# Charger.net
KiCad netlist of a schematic drawn in Altium Designer
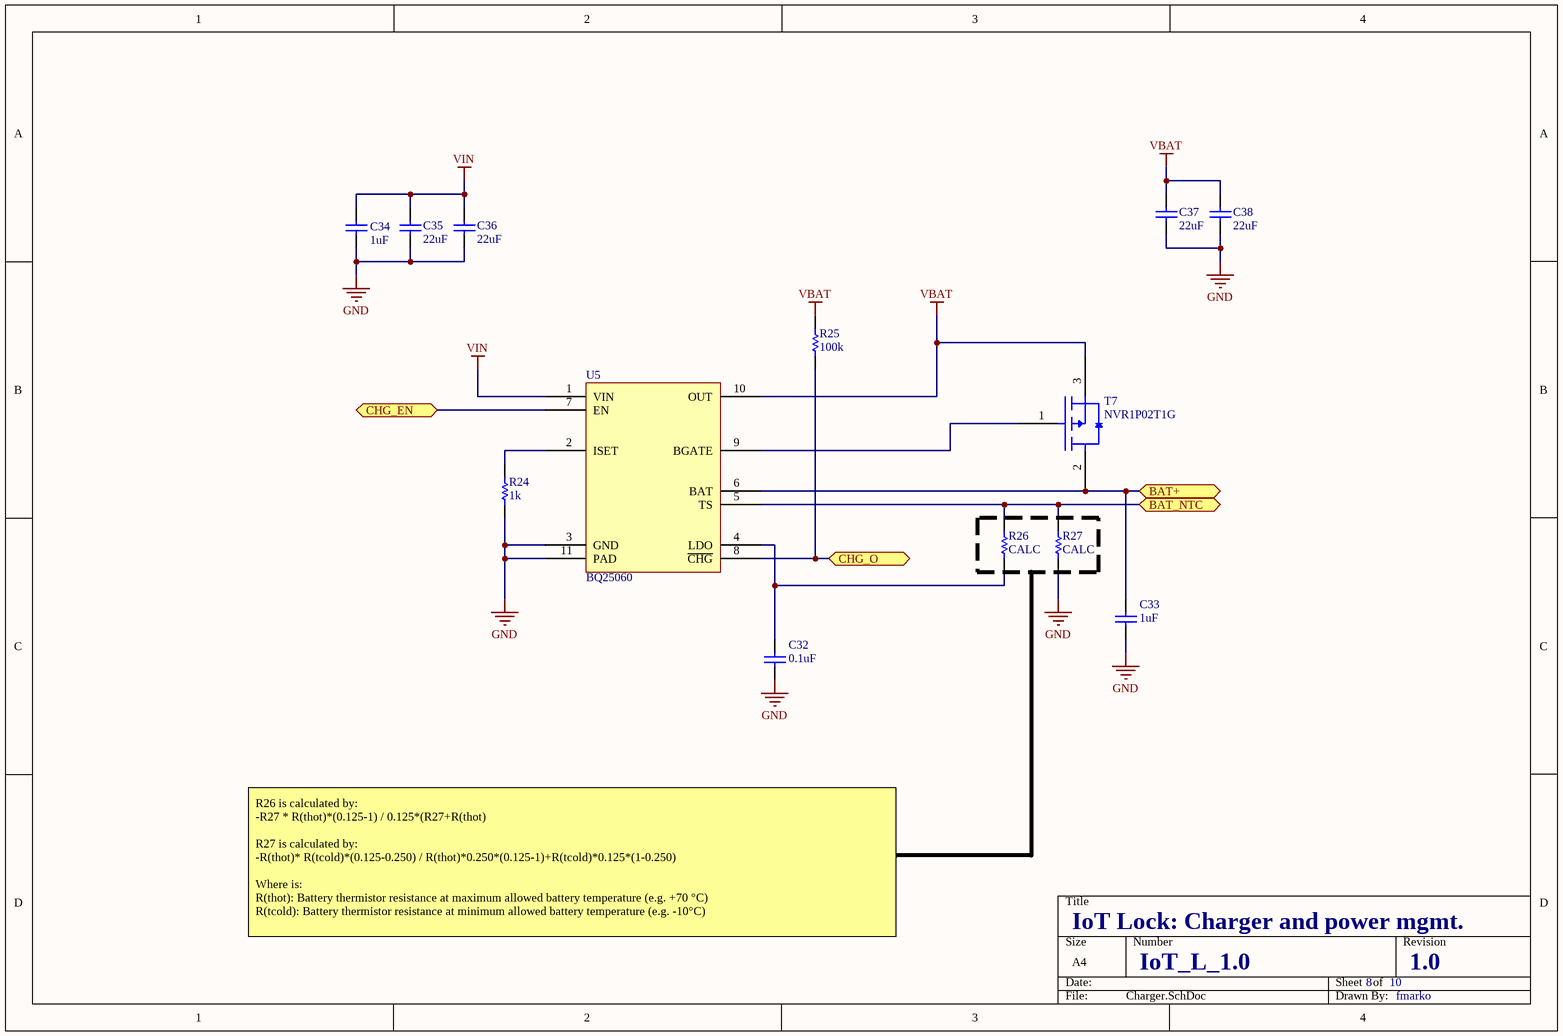
[diagram p0: Charger.SchDoc]

(export (version "E")
  (design (tool "Eeschema 10.0.6"))
  (components
    (comp (ref "C32")
      (value "0.1uF")
      (footprint "0402")
      (description "Capacitor")
      (fields (field (name "Comment") "GRM1555C1HR50BA01D") (field (name "PUBLISHER") "Altium Limited"))
      (libsource (lib "Miscellaneous Devices") (part "Cap"))
    )
    (comp (ref "C33")
      (value "1uF")
      (footprint "0402")
      (description "Capacitor")
      (fields (field (name "Comment") "GRM1555C1HR50BA01D") (field (name "PUBLISHER") "Altium Limited"))
      (libsource (lib "Miscellaneous Devices") (part "Cap"))
    )
    (comp (ref "C34")
      (value "1uF")
      (footprint "0402")
      (description "Capacitor")
      (fields (field (name "Comment") "GRM1555C1HR50BA01D") (field (name "PUBLISHER") "Altium Limited"))
      (libsource (lib "Miscellaneous Devices") (part "Cap"))
    )
    (comp (ref "C35")
      (value "22uF")
      (footprint "1608[0603]")
      (description "Capacitor")
      (fields (field (name "Comment") "GRM1555C1HR50BA01D") (field (name "PUBLISHER") "Altium Limited"))
      (libsource (lib "Miscellaneous Devices") (part "Cap"))
    )
    (comp (ref "C36")
      (value "22uF")
      (footprint "1608[0603]")
      (description "Capacitor")
      (fields (field (name "Comment") "GRM1555C1HR50BA01D") (field (name "PUBLISHER") "Altium Limited"))
      (libsource (lib "Miscellaneous Devices") (part "Cap"))
    )
    (comp (ref "C37")
      (value "22uF")
      (footprint "1608[0603]")
      (description "Capacitor")
      (fields (field (name "Comment") "GRM1555C1HR50BA01D") (field (name "PUBLISHER") "Altium Limited"))
      (libsource (lib "Miscellaneous Devices") (part "Cap"))
    )
    (comp (ref "C38")
      (value "22uF")
      (footprint "1608[0603]")
      (description "Capacitor")
      (fields (field (name "Comment") "GRM1555C1HR50BA01D") (field (name "PUBLISHER") "Altium Limited"))
      (libsource (lib "Miscellaneous Devices") (part "Cap"))
    )
    (comp (ref "R24")
      (value "1k")
      (footprint "0402")
      (description "Semiconductor Resistor")
      (fields (field (name "Comment") "Res Semi") (field (name "PUBLISHER") "Altium Limited"))
      (libsource (lib "Miscellaneous Devices") (part "Res Semi"))
    )
    (comp (ref "R25")
      (value "100k")
      (footprint "0402")
      (description "Semiconductor Resistor")
      (fields (field (name "Comment") "Res Semi") (field (name "PUBLISHER") "Altium Limited"))
      (libsource (lib "Miscellaneous Devices") (part "Res Semi"))
    )
    (comp (ref "R26")
      (value "CALC")
      (footprint "0402")
      (description "Semiconductor Resistor")
      (fields (field (name "Comment") "Res Semi") (field (name "PUBLISHER") "Altium Limited"))
      (libsource (lib "Miscellaneous Devices") (part "Res Semi"))
    )
    (comp (ref "R27")
      (value "CALC")
      (footprint "0402")
      (description "Semiconductor Resistor")
      (fields (field (name "Comment") "Res Semi") (field (name "PUBLISHER") "Altium Limited"))
      (libsource (lib "Miscellaneous Devices") (part "Res Semi"))
    )
    (comp (ref "T7")
      (value "NVR1P02T1G")
      (footprint "SOT95P237X111-3N")
      (description "P-Channel MOSFET")
      (libsource (lib "NVR1P02T1G") (part "NVR1P02T1G"))
    )
    (comp (ref "U5")
      (value "BQ25060")
      (footprint "SON50P200X80_HS-11N")
      (description "Li-Ion standalone charger, TI")
      (libsource (lib "BQ25060") (part "BQ25060"))
    )
  )
  (nets
    (net (code "1") (name "/BAT+") (class "Default")
      (node (ref "C33") (pin "2") (pinfunction "2_2") (pintype "passive"))
      (node (ref "T7") (pin "2") (pinfunction "S_2") (pintype "passive"))
      (node (ref "U5") (pin "6") (pinfunction "BAT_6") (pintype "passive"))
    )
    (net (code "2") (name "/BAT_NTC") (class "Default")
      (node (ref "R26") (pin "2") (pinfunction "2_2") (pintype "passive"))
      (node (ref "R27") (pin "2") (pinfunction "2_2") (pintype "passive"))
      (node (ref "U5") (pin "5") (pinfunction "TS_5") (pintype "passive"))
    )
    (net (code "3") (name "/CHG_EN") (class "Default")
      (node (ref "U5") (pin "7") (pinfunction "EN_7") (pintype "passive"))
    )
    (net (code "4") (name "/CHG_O") (class "Default")
      (node (ref "R25") (pin "1") (pinfunction "1_1") (pintype "passive"))
      (node (ref "U5") (pin "8") (pinfunction "~{CHG}_8") (pintype "passive"))
    )
    (net (code "5") (name "GND") (class "Default")
      (node (ref "C32") (pin "1") (pinfunction "1_1") (pintype "passive"))
      (node (ref "C33") (pin "1") (pinfunction "1_1") (pintype "passive"))
      (node (ref "C34") (pin "1") (pinfunction "1_1") (pintype "passive"))
      (node (ref "C35") (pin "1") (pinfunction "1_1") (pintype "passive"))
      (node (ref "C36") (pin "1") (pinfunction "1_1") (pintype "passive"))
      (node (ref "C37") (pin "1") (pinfunction "1_1") (pintype "passive"))
      (node (ref "C38") (pin "1") (pinfunction "1_1") (pintype "passive"))
      (node (ref "R24") (pin "1") (pinfunction "1_1") (pintype "passive"))
      (node (ref "R27") (pin "1") (pinfunction "1_1") (pintype "passive"))
      (node (ref "U5") (pin "11") (pinfunction "PAD_11") (pintype "passive"))
      (node (ref "U5") (pin "3") (pinfunction "GND_3") (pintype "passive"))
    )
    (net (code "6") (name "Net-(T7-G)") (class "Default")
      (node (ref "T7") (pin "1") (pinfunction "G_1") (pintype "passive"))
      (node (ref "U5") (pin "9") (pinfunction "BGATE_9") (pintype "passive"))
    )
    (net (code "7") (name "Net-(U5-ISET)") (class "Default")
      (node (ref "R24") (pin "2") (pinfunction "2_2") (pintype "passive"))
      (node (ref "U5") (pin "2") (pinfunction "ISET_2") (pintype "passive"))
    )
    (net (code "8") (name "Net-(U5-LDO)") (class "Default")
      (node (ref "C32") (pin "2") (pinfunction "2_2") (pintype "passive"))
      (node (ref "R26") (pin "1") (pinfunction "1_1") (pintype "passive"))
      (node (ref "U5") (pin "4") (pinfunction "LDO_4") (pintype "passive"))
    )
    (net (code "9") (name "VBAT") (class "Default")
      (node (ref "C37") (pin "2") (pinfunction "2_2") (pintype "passive"))
      (node (ref "C38") (pin "2") (pinfunction "2_2") (pintype "passive"))
      (node (ref "R25") (pin "2") (pinfunction "2_2") (pintype "passive"))
      (node (ref "T7") (pin "3") (pinfunction "D_3") (pintype "passive"))
      (node (ref "U5") (pin "10") (pinfunction "OUT_10") (pintype "passive"))
    )
    (net (code "10") (name "VIN") (class "Default")
      (node (ref "C34") (pin "2") (pinfunction "2_2") (pintype "passive"))
      (node (ref "C35") (pin "2") (pinfunction "2_2") (pintype "passive"))
      (node (ref "C36") (pin "2") (pinfunction "2_2") (pintype "passive"))
      (node (ref "U5") (pin "1") (pinfunction "VIN_1") (pintype "passive"))
    )
  )
)
